# Encoder_Brick.net
KiCad netlist of a schematic drawn in EAGLE
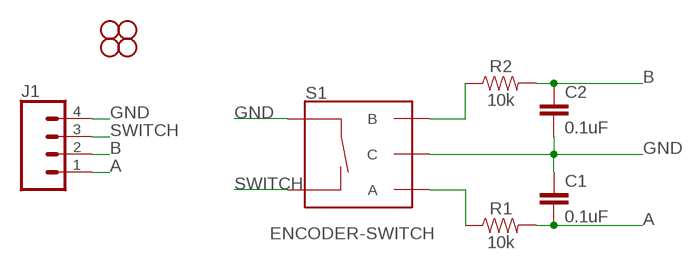
[diagram p0: schematic, sheet 1]

(export (version "E")
  (design (tool "Eeschema 10.0.6"))
  (components
    (comp (ref "C1")
      (value "0.1uF")
      (footprint "eagle-import:CAP-PTH-SMALL-KIT")
      (libsource (lib "eagle-import") (part "0.1UF-KIT-EZ-50V-20%"))
    )
    (comp (ref "C2")
      (value "0.1uF")
      (footprint "eagle-import:CAP-PTH-SMALL-KIT")
      (libsource (lib "eagle-import") (part "0.1UF-KIT-EZ-50V-20%"))
    )
    (comp (ref "J1")
      (value "CONN_04POLAR")
      (footprint "eagle-import:MOLEX-1X4")
      (libsource (lib "eagle-import") (part "CONN_04POLAR"))
    )
    (comp (ref "JP3")
      (value "STAND-OFF")
      (footprint "eagle-import:STAND-OFF")
      (libsource (lib "eagle-import") (part "STAND-OFF"))
    )
    (comp (ref "JP4")
      (value "STAND-OFF")
      (footprint "eagle-import:STAND-OFF")
      (libsource (lib "eagle-import") (part "STAND-OFF"))
    )
    (comp (ref "JP11")
      (value "STAND-OFF")
      (footprint "eagle-import:STAND-OFF")
      (libsource (lib "eagle-import") (part "STAND-OFF"))
    )
    (comp (ref "JP13")
      (value "STAND-OFF")
      (footprint "eagle-import:STAND-OFF")
      (libsource (lib "eagle-import") (part "STAND-OFF"))
    )
    (comp (ref "R1")
      (value "10k")
      (footprint "eagle-import:AXIAL-0.3-KIT")
      (libsource (lib "eagle-import") (part "10KOHM-HORIZ_KIT-1/4W-1%"))
    )
    (comp (ref "R2")
      (value "10k")
      (footprint "eagle-import:AXIAL-0.3-KIT")
      (libsource (lib "eagle-import") (part "10KOHM-HORIZ_KIT-1/4W-1%"))
    )
    (comp (ref "S1")
      (value "ENCODER-SWITCH")
      (footprint "eagle-import:ROTARY_ENC_PLAIN")
      (libsource (lib "eagle-import") (part "ENCODER-SWITCH"))
    )
  )
  (nets
    (net (code "1") (name "/A") (class "Default")
      (node (ref "C1") (pin "2") (pinfunction "2_2") (pintype "passive"))
      (node (ref "J1") (pin "1") (pinfunction "1_1") (pintype "passive"))
      (node (ref "R1") (pin "P$2") (pinfunction "2_P$2") (pintype "passive"))
    )
    (net (code "2") (name "/B") (class "Default")
      (node (ref "C2") (pin "1") (pinfunction "1_1") (pintype "passive"))
      (node (ref "J1") (pin "2") (pinfunction "2_2") (pintype "passive"))
      (node (ref "R2") (pin "P$2") (pinfunction "2_P$2") (pintype "passive"))
    )
    (net (code "3") (name "/GND") (class "Default")
      (node (ref "C1") (pin "1") (pinfunction "1_1") (pintype "passive"))
      (node (ref "C2") (pin "2") (pinfunction "2_2") (pintype "passive"))
      (node (ref "J1") (pin "4") (pinfunction "4_4") (pintype "passive"))
      (node (ref "S1") (pin "C") (pinfunction "C_C") (pintype "bidirectional"))
      (node (ref "S1") (pin "SW+") (pinfunction "SW+_SW+") (pintype "bidirectional"))
    )
    (net (code "4") (name "/SWITCH") (class "Default")
      (node (ref "J1") (pin "3") (pinfunction "3_3") (pintype "passive"))
      (node (ref "S1") (pin "SW-") (pinfunction "SW-_SW-") (pintype "bidirectional"))
    )
    (net (code "5") (name "Net-(R1-1)") (class "Default")
      (node (ref "R1") (pin "P$1") (pinfunction "1_P$1") (pintype "passive"))
      (node (ref "S1") (pin "A") (pinfunction "A_A") (pintype "bidirectional"))
    )
    (net (code "6") (name "Net-(R2-1)") (class "Default")
      (node (ref "R2") (pin "P$1") (pinfunction "1_P$1") (pintype "passive"))
      (node (ref "S1") (pin "B") (pinfunction "B_B") (pintype "bidirectional"))
    )
  )
)
